# power-supply.net
KiCad netlist of a schematic drawn in EAGLE
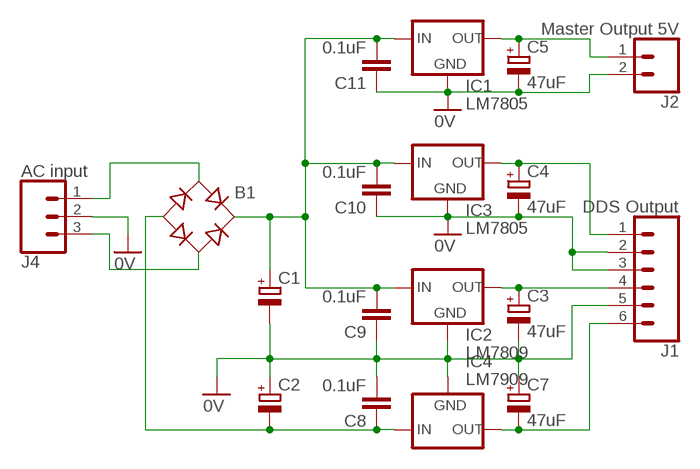
[diagram p0: schematic, sheet 1]

(export (version "E")
  (design (tool "Eeschema 10.0.6"))
  (components
    (comp (ref "B1")
      (value "RB1A")
      (footprint "eagle-import:RB1A")
      (libsource (lib "eagle-import") (part "RB1A"))
    )
    (comp (ref "C1")
      (value "CPOL-EUE7.5-16")
      (footprint "eagle-import:E7,5-16")
      (libsource (lib "eagle-import") (part "CPOL-EUE7.5-16"))
    )
    (comp (ref "C2")
      (value "CPOL-EUE7.5-16")
      (footprint "eagle-import:E7,5-16")
      (libsource (lib "eagle-import") (part "CPOL-EUE7.5-16"))
    )
    (comp (ref "C3")
      (value "47uF")
      (footprint "eagle-import:E5-6")
      (libsource (lib "eagle-import") (part "CPOL-EUE5-6"))
    )
    (comp (ref "C4")
      (value "47uF")
      (footprint "eagle-import:E5-6")
      (libsource (lib "eagle-import") (part "CPOL-EUE5-6"))
    )
    (comp (ref "C5")
      (value "47uF")
      (footprint "eagle-import:E2,5-6")
      (libsource (lib "eagle-import") (part "CPOL-EUE2.5-6"))
    )
    (comp (ref "C7")
      (value "47uF")
      (footprint "eagle-import:E5-6")
      (libsource (lib "eagle-import") (part "CPOL-EUE5-6"))
    )
    (comp (ref "C8")
      (value "0.1uF")
      (footprint "eagle-import:C025-025X050")
      (libsource (lib "eagle-import") (part "C-EU025-025X050"))
    )
    (comp (ref "C9")
      (value "0.1uF")
      (footprint "eagle-import:C025-025X050")
      (libsource (lib "eagle-import") (part "C-EU025-025X050"))
    )
    (comp (ref "C10")
      (value "0.1uF")
      (footprint "eagle-import:C025-025X050")
      (libsource (lib "eagle-import") (part "C-EU025-025X050"))
    )
    (comp (ref "C11")
      (value "0.1uF")
      (footprint "eagle-import:C025-025X050")
      (libsource (lib "eagle-import") (part "C-EU025-025X050"))
    )
    (comp (ref "IC1")
      (value "LM7805")
      (footprint "eagle-import:78XXS")
      (libsource (lib "eagle-import") (part "78XXS"))
    )
    (comp (ref "IC2")
      (value "LM7809")
      (footprint "eagle-import:78XXS")
      (libsource (lib "eagle-import") (part "78XXS"))
    )
    (comp (ref "IC3")
      (value "LM7805")
      (footprint "eagle-import:78XXS")
      (libsource (lib "eagle-import") (part "78XXS"))
    )
    (comp (ref "IC4")
      (value "LM7909")
      (footprint "eagle-import:79XXS")
      (libsource (lib "eagle-import") (part "79XXS"))
    )
    (comp (ref "J1")
      (value "DDS Output")
      (footprint "eagle-import:MOLEX-1X6")
      (libsource (lib "eagle-import") (part "CONN_06POLAR"))
    )
    (comp (ref "J2")
      (value "Master Output 5V")
      (footprint "eagle-import:MOLEX-1X2")
      (libsource (lib "eagle-import") (part "CONN_02POLAR"))
    )
    (comp (ref "J4")
      (value "AC input")
      (footprint "eagle-import:MOLEX-1X3")
      (libsource (lib "eagle-import") (part "CONN_03POLAR"))
    )
  )
  (nets
    (net (code "1") (name "0V") (class "Default")
      (node (ref "C1") (pin "-") (pinfunction "-_-") (pintype "passive"))
      (node (ref "C10") (pin "1") (pinfunction "1_1") (pintype "passive"))
      (node (ref "C11") (pin "1") (pinfunction "1_1") (pintype "passive"))
      (node (ref "C2") (pin "+") (pinfunction "+_+") (pintype "passive"))
      (node (ref "C3") (pin "-") (pinfunction "-_-") (pintype "passive"))
      (node (ref "C4") (pin "-") (pinfunction "-_-") (pintype "passive"))
      (node (ref "C5") (pin "-") (pinfunction "-_-") (pintype "passive"))
      (node (ref "C7") (pin "+") (pinfunction "+_+") (pintype "passive"))
      (node (ref "C8") (pin "2") (pinfunction "2_2") (pintype "passive"))
      (node (ref "C9") (pin "1") (pinfunction "1_1") (pintype "passive"))
      (node (ref "IC1") (pin "GND") (pinfunction "GND_GND") (pintype "input"))
      (node (ref "IC2") (pin "GND") (pinfunction "GND_GND") (pintype "input"))
      (node (ref "IC3") (pin "GND") (pinfunction "GND_GND") (pintype "input"))
      (node (ref "IC4") (pin "GND") (pinfunction "GND_GND") (pintype "input"))
      (node (ref "J1") (pin "2") (pinfunction "2_2") (pintype "passive"))
      (node (ref "J1") (pin "3") (pinfunction "3_3") (pintype "passive"))
      (node (ref "J1") (pin "5") (pinfunction "5_5") (pintype "passive"))
      (node (ref "J2") (pin "2") (pinfunction "2_2") (pintype "passive"))
      (node (ref "J4") (pin "2") (pinfunction "2_2") (pintype "passive"))
    )
    (net (code "2") (name "Net-(B1-Pad+)") (class "Default")
      (node (ref "B1") (pin "+") (pinfunction "+_+") (pintype "passive"))
      (node (ref "C1") (pin "+") (pinfunction "+_+") (pintype "passive"))
      (node (ref "C10") (pin "2") (pinfunction "2_2") (pintype "passive"))
      (node (ref "C11") (pin "2") (pinfunction "2_2") (pintype "passive"))
      (node (ref "C9") (pin "2") (pinfunction "2_2") (pintype "passive"))
      (node (ref "IC1") (pin "IN") (pinfunction "IN_IN") (pintype "input"))
      (node (ref "IC2") (pin "IN") (pinfunction "IN_IN") (pintype "input"))
      (node (ref "IC3") (pin "IN") (pinfunction "IN_IN") (pintype "input"))
    )
    (net (code "3") (name "Net-(B1-Pad-)") (class "Default")
      (node (ref "B1") (pin "-") (pinfunction "-_-") (pintype "passive"))
      (node (ref "C2") (pin "-") (pinfunction "-_-") (pintype "passive"))
      (node (ref "C8") (pin "1") (pinfunction "1_1") (pintype "passive"))
      (node (ref "IC4") (pin "IN") (pinfunction "IN_IN") (pintype "input"))
    )
    (net (code "4") (name "Net-(B1-PadAC1)") (class "Default")
      (node (ref "B1") (pin "AC1") (pinfunction "AC1_AC1") (pintype "passive"))
      (node (ref "J4") (pin "1") (pinfunction "1_1") (pintype "passive"))
    )
    (net (code "5") (name "Net-(B1-PadAC2)") (class "Default")
      (node (ref "B1") (pin "AC2") (pinfunction "AC2_AC2") (pintype "passive"))
      (node (ref "J4") (pin "3") (pinfunction "3_3") (pintype "passive"))
    )
    (net (code "6") (name "Net-(C3-Pad+)") (class "Default")
      (node (ref "C3") (pin "+") (pinfunction "+_+") (pintype "passive"))
      (node (ref "IC2") (pin "OUT") (pinfunction "OUT_OUT") (pintype "passive"))
      (node (ref "J1") (pin "4") (pinfunction "4_4") (pintype "passive"))
    )
    (net (code "7") (name "Net-(C4-Pad+)") (class "Default")
      (node (ref "C4") (pin "+") (pinfunction "+_+") (pintype "passive"))
      (node (ref "IC3") (pin "OUT") (pinfunction "OUT_OUT") (pintype "passive"))
      (node (ref "J1") (pin "1") (pinfunction "1_1") (pintype "passive"))
    )
    (net (code "8") (name "Net-(C5-Pad+)") (class "Default")
      (node (ref "C5") (pin "+") (pinfunction "+_+") (pintype "passive"))
      (node (ref "IC1") (pin "OUT") (pinfunction "OUT_OUT") (pintype "passive"))
      (node (ref "J2") (pin "1") (pinfunction "1_1") (pintype "passive"))
    )
    (net (code "9") (name "Net-(C7-Pad-)") (class "Default")
      (node (ref "C7") (pin "-") (pinfunction "-_-") (pintype "passive"))
      (node (ref "IC4") (pin "OUT") (pinfunction "OUT_OUT") (pintype "passive"))
      (node (ref "J1") (pin "6") (pinfunction "6_6") (pintype "passive"))
    )
  )
)
